# CATS-FAT-Pyro.net
KiCad netlist of a schematic drawn in Altium Designer
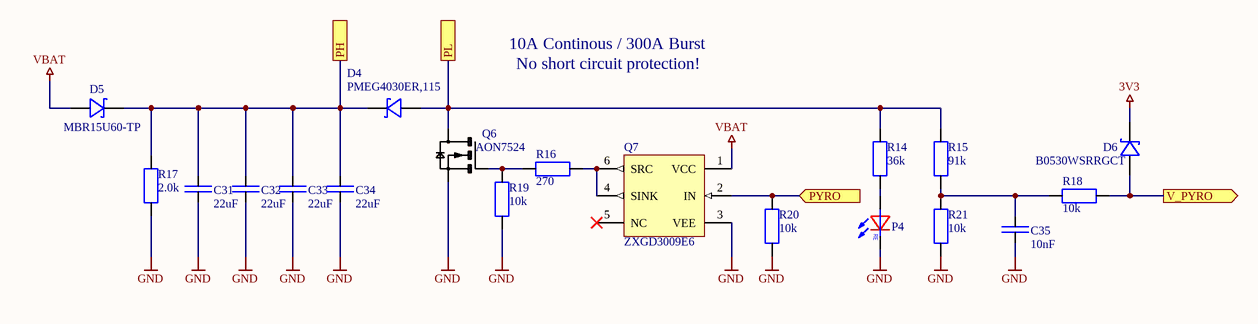
[diagram p0: CATS-FAT-Pyro.SchDoc]

(export (version "E")
  (design (tool "Eeschema 10.0.6"))
  (components
    (comp (ref "C31")
      (value "22uF")
      (footprint "SMD Keramikkondensator 0805")
      (description "SMD Ceramic Capacitor E6")
      (libsource (lib "Ceramic Capacitors-E6") (part "E6 - 22uF"))
    )
    (comp (ref "C32")
      (value "22uF")
      (footprint "SMD Keramikkondensator 0805")
      (description "SMD Ceramic Capacitor E6")
      (libsource (lib "Ceramic Capacitors-E6") (part "E6 - 22uF"))
    )
    (comp (ref "C33")
      (value "22uF")
      (footprint "SMD Keramikkondensator 0805")
      (description "SMD Ceramic Capacitor E6")
      (libsource (lib "Ceramic Capacitors-E6") (part "E6 - 22uF"))
    )
    (comp (ref "C34")
      (value "22uF")
      (footprint "SMD Keramikkondensator 0805")
      (description "SMD Ceramic Capacitor E6")
      (libsource (lib "Ceramic Capacitors-E6") (part "E6 - 22uF"))
    )
    (comp (ref "C35")
      (value "10nF")
      (footprint "SMD Keramikkondensator 0603")
      (description "SMD Ceramic Capacitor E6")
      (libsource (lib "Ceramic Capacitors-E6") (part "E6 - 10nF"))
    )
    (comp (ref "D4")
      (value "PMEG4030ER,115")
      (footprint "SMD Diode SOD-123")
      (description "Diode Schottky 3A Surface Mount CFP3")
      (libsource (lib "Diodes") (part "PMEG4030ER,115"))
    )
    (comp (ref "D5")
      (value "MBR15U60-TP")
      (footprint "SMD Diode TO-277")
      (description "Diode Schottky 15A Surface Mount TO-277-3")
      (libsource (lib "Diodes") (part "MBR15U60-TP"))
    )
    (comp (ref "D6")
      (value "B0530WSRRGCT")
      (footprint "SMD Diode SOD-323F")
      (description "200mW, 0.47V Schottky Barrier Diode")
      (libsource (lib "Diodes") (part "B0530WSRRGCT"))
    )
    (comp (ref "P4")
      (value "LED")
      (footprint "SMD LED 0603")
      (description "Color LED")
      (libsource (lib "Diodes") (part "LED"))
    )
    (comp (ref "Q6")
      (value "AON7524")
      (footprint "SMD MOSFET DFN 3x3 EP")
      (description "N-Channel 30V 25A (Ta), 28A (Tc) 3.1W (Ta), 32W (Tc) Surface Mount 8-DFN (3x3)")
      (libsource (lib "Electronic Switches") (part "AON7524"))
    )
    (comp (ref "Q7")
      (value "ZXGD3009E6")
      (footprint "SMD IC SOT-23-6")
      (description "Low-Side Gate Driver IC Non-Inverting SOT-26")
      (libsource (lib "Electronic Switches") (part "ZXGD3009E6"))
    )
    (comp (ref "R14")
      (value "36k")
      (footprint "SMD Widerstand 0603")
      (description "SMD Chip Resistor E24")
      (libsource (lib "Resistors-E24") (part "E24 - 36k"))
    )
    (comp (ref "R15")
      (value "91k")
      (footprint "SMD Widerstand 0603")
      (description "SMD Chip Resistor E24")
      (libsource (lib "Resistors-E24") (part "E24 - 91k"))
    )
    (comp (ref "R16")
      (value "270")
      (footprint "SMD Widerstand 0603")
      (description "SMD Chip Resistor E24")
      (libsource (lib "Resistors-E24") (part "E24 - 270"))
    )
    (comp (ref "R17")
      (value "2.0k")
      (footprint "SMD Widerstand 0603")
      (description "SMD Chip Resistor E24")
      (libsource (lib "Resistors-E24") (part "E24 - 2.0k"))
    )
    (comp (ref "R18")
      (value "10k")
      (footprint "SMD Widerstand 0603")
      (description "SMD Chip Resistor E24")
      (libsource (lib "") (part "E24 - 10k_1"))
    )
    (comp (ref "R19")
      (value "10k")
      (footprint "SMD Widerstand 0603")
      (description "SMD Chip Resistor E24")
      (libsource (lib "Resistors-E24") (part "E24 - 10k"))
    )
    (comp (ref "R20")
      (value "10k")
      (footprint "SMD Widerstand 0603")
      (description "SMD Chip Resistor E24")
      (libsource (lib "Resistors-E24") (part "E24 - 10k"))
    )
    (comp (ref "R21")
      (value "10k")
      (footprint "SMD Widerstand 0603")
      (description "SMD Chip Resistor E24")
      (libsource (lib "Resistors-E24") (part "E24 - 10k"))
    )
  )
  (nets
    (net (code "1") (name "/PH") (class "Default")
      (node (ref "C31") (pin "2") (pinfunction "2_2") (pintype "passive"))
      (node (ref "C32") (pin "2") (pinfunction "2_2") (pintype "passive"))
      (node (ref "C33") (pin "2") (pinfunction "2_2") (pintype "passive"))
      (node (ref "C34") (pin "2") (pinfunction "2_2") (pintype "passive"))
      (node (ref "D4") (pin "K") (pinfunction "K_K") (pintype "passive"))
      (node (ref "D5") (pin "K") (pinfunction "K_K") (pintype "passive"))
      (node (ref "R17") (pin "2") (pinfunction "2_2") (pintype "passive"))
    )
    (net (code "2") (name "/PL") (class "Default")
      (node (ref "D4") (pin "A") (pinfunction "A_A") (pintype "passive"))
      (node (ref "Q6") (pin "D") (pinfunction "D_D") (pintype "passive"))
      (node (ref "R14") (pin "2") (pinfunction "2_2") (pintype "passive"))
      (node (ref "R15") (pin "2") (pinfunction "2_2") (pintype "passive"))
    )
    (net (code "3") (name "/PYRO") (class "Default")
      (node (ref "Q7") (pin "2") (pinfunction "IN_2") (pintype "input"))
      (node (ref "R20") (pin "2") (pinfunction "2_2") (pintype "passive"))
    )
    (net (code "4") (name "/V_PYRO") (class "Default")
      (node (ref "D6") (pin "A") (pinfunction "A_A") (pintype "passive"))
      (node (ref "R18") (pin "1") (pinfunction "1_1") (pintype "passive"))
    )
    (net (code "5") (name "3V3") (class "Default")
      (node (ref "D6") (pin "K") (pinfunction "K_K") (pintype "passive"))
    )
    (net (code "6") (name "GND") (class "Default")
      (node (ref "C31") (pin "1") (pinfunction "1_1") (pintype "passive"))
      (node (ref "C32") (pin "1") (pinfunction "1_1") (pintype "passive"))
      (node (ref "C33") (pin "1") (pinfunction "1_1") (pintype "passive"))
      (node (ref "C34") (pin "1") (pinfunction "1_1") (pintype "passive"))
      (node (ref "C35") (pin "1") (pinfunction "1_1") (pintype "passive"))
      (node (ref "P4") (pin "K") (pinfunction "K_K") (pintype "passive"))
      (node (ref "Q6") (pin "S") (pinfunction "S_S") (pintype "passive"))
      (node (ref "Q7") (pin "3") (pinfunction "VEE_3") (pintype "passive"))
      (node (ref "R17") (pin "1") (pinfunction "1_1") (pintype "passive"))
      (node (ref "R19") (pin "1") (pinfunction "1_1") (pintype "passive"))
      (node (ref "R20") (pin "1") (pinfunction "1_1") (pintype "passive"))
      (node (ref "R21") (pin "1") (pinfunction "1_1") (pintype "passive"))
    )
    (net (code "7") (name "Net-(C35-Pad2)") (class "Default")
      (node (ref "C35") (pin "2") (pinfunction "2_2") (pintype "passive"))
      (node (ref "R15") (pin "1") (pinfunction "1_1") (pintype "passive"))
      (node (ref "R18") (pin "2") (pinfunction "2_2") (pintype "passive"))
      (node (ref "R21") (pin "2") (pinfunction "2_2") (pintype "passive"))
    )
    (net (code "8") (name "Net-(P4-PadA)") (class "Default")
      (node (ref "P4") (pin "A") (pinfunction "A_A") (pintype "passive"))
      (node (ref "R14") (pin "1") (pinfunction "1_1") (pintype "passive"))
    )
    (net (code "9") (name "Net-(Q6-PadG)") (class "Default")
      (node (ref "Q6") (pin "G") (pinfunction "G_G") (pintype "passive"))
      (node (ref "R16") (pin "1") (pinfunction "1_1") (pintype "passive"))
      (node (ref "R19") (pin "2") (pinfunction "2_2") (pintype "passive"))
    )
    (net (code "10") (name "Net-(Q7-SINK)") (class "Default")
      (node (ref "Q7") (pin "4") (pinfunction "SINK_4") (pintype "output"))
      (node (ref "Q7") (pin "6") (pinfunction "SRC_6") (pintype "output"))
      (node (ref "R16") (pin "2") (pinfunction "2_2") (pintype "passive"))
    )
    (net (code "11") (name "VBAT") (class "Default")
      (node (ref "D5") (pin "A") (pinfunction "A_A") (pintype "passive"))
      (node (ref "Q7") (pin "1") (pinfunction "VCC_1") (pintype "passive"))
    )
    (net (code "12") (name "unconnected-(Q7-NC-Pad5)") (class "Default")
      (node (ref "Q7") (pin "5") (pinfunction "NC_5") (pintype "passive+no_connect"))
    )
  )
)
